# Phychip_board.net
KiCad netlist of a schematic drawn in EAGLE
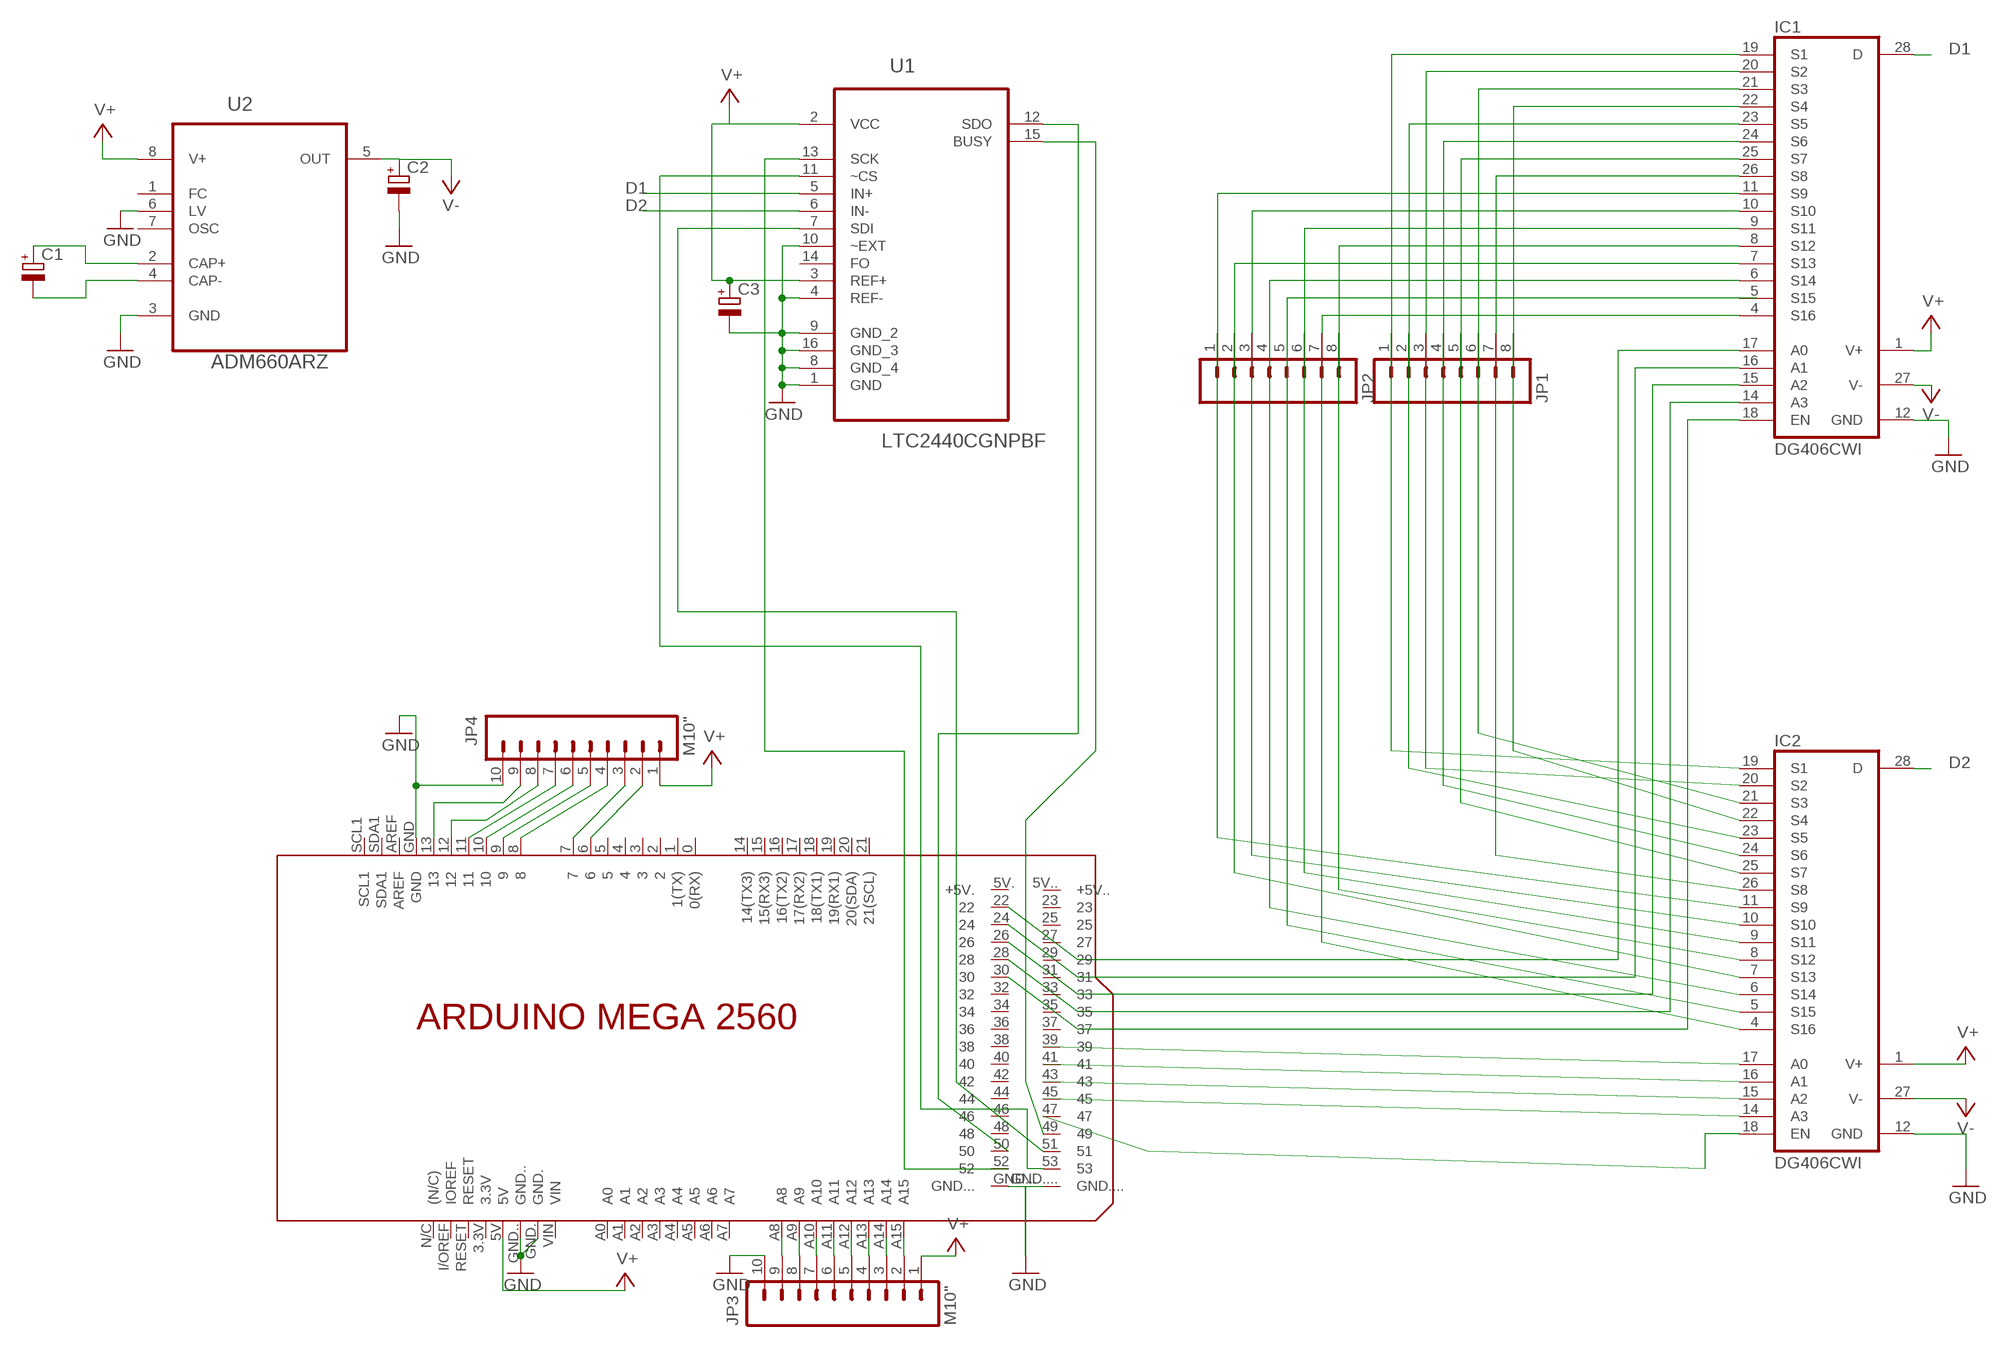
[diagram p0: schematic, sheet 1]

(export (version "E")
  (design (tool "Eeschema 10.0.6"))
  (components
    (comp (ref "C1")
      (value "CPOL-EUE5-6")
      (footprint "eagle-import:E5-6")
      (libsource (lib "eagle-import") (part "CPOL-EUE5-6"))
    )
    (comp (ref "C2")
      (value "CPOL-EUE5-6")
      (footprint "eagle-import:E5-6")
      (libsource (lib "eagle-import") (part "CPOL-EUE5-6"))
    )
    (comp (ref "C3")
      (value "CPOL-EUE5-6")
      (footprint "eagle-import:E5-6")
      (libsource (lib "eagle-import") (part "CPOL-EUE5-6"))
    )
    (comp (ref "IC1")
      (value "DG406CWI")
      (footprint "eagle-import:SO28L")
      (fields (field (name "MF") "MAXIM"))
      (libsource (lib "eagle-import") (part "DG406CWI"))
    )
    (comp (ref "IC2")
      (value "DG406CWI")
      (footprint "eagle-import:SO28L")
      (fields (field (name "MF") "MAXIM"))
      (libsource (lib "eagle-import") (part "DG406CWI"))
    )
    (comp (ref "JP1")
      (value "M08")
      (footprint "eagle-import:1X08")
      (libsource (lib "eagle-import") (part "M08"))
    )
    (comp (ref "JP2")
      (value "M08")
      (footprint "eagle-import:1X08")
      (libsource (lib "eagle-import") (part "M08"))
    )
    (comp (ref "JP3")
      (value "M10\"")
      (footprint "eagle-import:1X10")
      (libsource (lib "eagle-import") (part "M10{dblquote}"))
    )
    (comp (ref "JP4")
      (value "M10\"")
      (footprint "eagle-import:1X10")
      (libsource (lib "eagle-import") (part "M10{dblquote}"))
    )
    (comp (ref "PCB1")
      (value "ARDUINO_MEGA2560")
      (footprint "eagle-import:ARDUINO_MEGA2560")
      (libsource (lib "eagle-import") (part "ARDUINO_MEGA2560"))
    )
    (comp (ref "U1")
      (value "LTC2440CGNPBF")
      (footprint "eagle-import:SOP63P600X175-16N")
      (fields (field (name "MPN") "LTC2440CGN#PBF"))
      (libsource (lib "eagle-import") (part "LTC2440CGNPBF"))
    )
    (comp (ref "U2")
      (value "ADM660ARZ")
      (footprint "eagle-import:SOIC127P600X175-8N")
      (libsource (lib "eagle-import") (part "ADM660ARZ"))
    )
  )
  (nets
    (net (code "1") (name "/D1") (class "Default")
      (node (ref "IC1") (pin "28") (pinfunction "D_28") (pintype "passive"))
      (node (ref "U1") (pin "5") (pinfunction "IN+_5") (pintype "input"))
    )
    (net (code "2") (name "/D2") (class "Default")
      (node (ref "IC2") (pin "28") (pinfunction "D_28") (pintype "passive"))
      (node (ref "U1") (pin "6") (pinfunction "IN-_6") (pintype "input"))
    )
    (net (code "3") (name "GND") (class "Default")
      (node (ref "C2") (pin "-") (pinfunction "-_-") (pintype "passive"))
      (node (ref "C3") (pin "-") (pinfunction "-_-") (pintype "passive"))
      (node (ref "IC1") (pin "12") (pinfunction "GND_12") (pintype "power_in"))
      (node (ref "IC2") (pin "12") (pinfunction "GND_12") (pintype "power_in"))
      (node (ref "JP3") (pin "10") (pinfunction "10_10") (pintype "passive"))
      (node (ref "JP4") (pin "10") (pinfunction "10_10") (pintype "passive"))
      (node (ref "PCB1") (pin "GND") (pinfunction "GND_GND") (pintype "bidirectional"))
      (node (ref "PCB1") (pin "GND.") (pinfunction "GND._GND.") (pintype "bidirectional"))
      (node (ref "PCB1") (pin "GND..") (pinfunction "GND.._GND..") (pintype "bidirectional"))
      (node (ref "PCB1") (pin "GND...") (pinfunction "GND..._GND...") (pintype "bidirectional"))
      (node (ref "PCB1") (pin "GND....") (pinfunction "GND...._GND....") (pintype "bidirectional"))
      (node (ref "U1") (pin "1") (pinfunction "GND_1") (pintype "passive"))
      (node (ref "U1") (pin "10") (pinfunction "~{EXT}_10") (pintype "input"))
      (node (ref "U1") (pin "16") (pinfunction "GND_3_16") (pintype "passive"))
      (node (ref "U1") (pin "4") (pinfunction "REF-_4") (pintype "input"))
      (node (ref "U1") (pin "8") (pinfunction "GND_4_8") (pintype "passive"))
      (node (ref "U1") (pin "9") (pinfunction "GND_2_9") (pintype "passive"))
      (node (ref "U2") (pin "3") (pinfunction "GND_3") (pintype "passive"))
      (node (ref "U2") (pin "6") (pinfunction "LV_6") (pintype "input"))
    )
    (net (code "4") (name "Net-(IC1-A0)") (class "Default")
      (node (ref "IC1") (pin "17") (pinfunction "A0_17") (pintype "input"))
      (node (ref "PCB1") (pin "22") (pinfunction "22_22") (pintype "bidirectional"))
    )
    (net (code "5") (name "Net-(IC1-A1)") (class "Default")
      (node (ref "IC1") (pin "16") (pinfunction "A1_16") (pintype "input"))
      (node (ref "PCB1") (pin "24") (pinfunction "24_24") (pintype "bidirectional"))
    )
    (net (code "6") (name "Net-(IC1-A2)") (class "Default")
      (node (ref "IC1") (pin "15") (pinfunction "A2_15") (pintype "input"))
      (node (ref "PCB1") (pin "26") (pinfunction "26_26") (pintype "bidirectional"))
    )
    (net (code "7") (name "Net-(IC1-A3)") (class "Default")
      (node (ref "IC1") (pin "14") (pinfunction "A3_14") (pintype "input"))
      (node (ref "PCB1") (pin "28") (pinfunction "28_28") (pintype "bidirectional"))
    )
    (net (code "8") (name "Net-(IC1-EN)") (class "Default")
      (node (ref "IC1") (pin "18") (pinfunction "EN_18") (pintype "input"))
      (node (ref "PCB1") (pin "30") (pinfunction "30_30") (pintype "bidirectional"))
    )
    (net (code "9") (name "Net-(IC1-S1)") (class "Default")
      (node (ref "IC1") (pin "19") (pinfunction "S1_19") (pintype "passive"))
      (node (ref "IC2") (pin "19") (pinfunction "S1_19") (pintype "passive"))
      (node (ref "JP1") (pin "1") (pinfunction "1_1") (pintype "passive"))
    )
    (net (code "10") (name "Net-(IC1-S2)") (class "Default")
      (node (ref "IC1") (pin "20") (pinfunction "S2_20") (pintype "passive"))
      (node (ref "IC2") (pin "20") (pinfunction "S2_20") (pintype "passive"))
      (node (ref "JP1") (pin "3") (pinfunction "3_3") (pintype "passive"))
    )
    (net (code "11") (name "Net-(IC1-S3)") (class "Default")
      (node (ref "IC1") (pin "21") (pinfunction "S3_21") (pintype "passive"))
      (node (ref "IC2") (pin "21") (pinfunction "S3_21") (pintype "passive"))
      (node (ref "JP1") (pin "6") (pinfunction "6_6") (pintype "passive"))
    )
    (net (code "12") (name "Net-(IC1-S4)") (class "Default")
      (node (ref "IC1") (pin "22") (pinfunction "S4_22") (pintype "passive"))
      (node (ref "IC2") (pin "22") (pinfunction "S4_22") (pintype "passive"))
      (node (ref "JP1") (pin "8") (pinfunction "8_8") (pintype "passive"))
    )
    (net (code "13") (name "Net-(IC1-S5)") (class "Default")
      (node (ref "IC1") (pin "23") (pinfunction "S5_23") (pintype "passive"))
      (node (ref "IC2") (pin "23") (pinfunction "S5_23") (pintype "passive"))
      (node (ref "JP1") (pin "2") (pinfunction "2_2") (pintype "passive"))
    )
    (net (code "14") (name "Net-(IC1-S6)") (class "Default")
      (node (ref "IC1") (pin "24") (pinfunction "S6_24") (pintype "passive"))
      (node (ref "IC2") (pin "24") (pinfunction "S6_24") (pintype "passive"))
      (node (ref "JP1") (pin "4") (pinfunction "4_4") (pintype "passive"))
    )
    (net (code "15") (name "Net-(IC1-S7)") (class "Default")
      (node (ref "IC1") (pin "25") (pinfunction "S7_25") (pintype "passive"))
      (node (ref "IC2") (pin "25") (pinfunction "S7_25") (pintype "passive"))
      (node (ref "JP1") (pin "5") (pinfunction "5_5") (pintype "passive"))
    )
    (net (code "16") (name "Net-(IC1-S8)") (class "Default")
      (node (ref "IC1") (pin "26") (pinfunction "S8_26") (pintype "passive"))
      (node (ref "IC2") (pin "26") (pinfunction "S8_26") (pintype "passive"))
      (node (ref "JP1") (pin "7") (pinfunction "7_7") (pintype "passive"))
    )
    (net (code "17") (name "Net-(IC1-S9)") (class "Default")
      (node (ref "IC1") (pin "11") (pinfunction "S9_11") (pintype "passive"))
      (node (ref "IC2") (pin "11") (pinfunction "S9_11") (pintype "passive"))
      (node (ref "JP2") (pin "1") (pinfunction "1_1") (pintype "passive"))
    )
    (net (code "18") (name "Net-(IC1-S10)") (class "Default")
      (node (ref "IC1") (pin "10") (pinfunction "S10_10") (pintype "passive"))
      (node (ref "IC2") (pin "10") (pinfunction "S10_10") (pintype "passive"))
      (node (ref "JP2") (pin "3") (pinfunction "3_3") (pintype "passive"))
    )
    (net (code "19") (name "Net-(IC1-S11)") (class "Default")
      (node (ref "IC1") (pin "9") (pinfunction "S11_9") (pintype "passive"))
      (node (ref "IC2") (pin "9") (pinfunction "S11_9") (pintype "passive"))
      (node (ref "JP2") (pin "6") (pinfunction "6_6") (pintype "passive"))
    )
    (net (code "20") (name "Net-(IC1-S12)") (class "Default")
      (node (ref "IC1") (pin "8") (pinfunction "S12_8") (pintype "passive"))
      (node (ref "IC2") (pin "8") (pinfunction "S12_8") (pintype "passive"))
      (node (ref "JP2") (pin "8") (pinfunction "8_8") (pintype "passive"))
    )
    (net (code "21") (name "Net-(IC1-S13)") (class "Default")
      (node (ref "IC1") (pin "7") (pinfunction "S13_7") (pintype "passive"))
      (node (ref "IC2") (pin "7") (pinfunction "S13_7") (pintype "passive"))
      (node (ref "JP2") (pin "2") (pinfunction "2_2") (pintype "passive"))
    )
    (net (code "22") (name "Net-(IC1-S14)") (class "Default")
      (node (ref "IC1") (pin "6") (pinfunction "S14_6") (pintype "passive"))
      (node (ref "IC2") (pin "6") (pinfunction "S14_6") (pintype "passive"))
      (node (ref "JP2") (pin "4") (pinfunction "4_4") (pintype "passive"))
    )
    (net (code "23") (name "Net-(IC1-S16)") (class "Default")
      (node (ref "IC1") (pin "4") (pinfunction "S16_4") (pintype "passive"))
      (node (ref "IC2") (pin "4") (pinfunction "S16_4") (pintype "passive"))
      (node (ref "JP2") (pin "7") (pinfunction "7_7") (pintype "passive"))
    )
    (net (code "24") (name "Net-(IC2-A0)") (class "Default")
      (node (ref "IC2") (pin "17") (pinfunction "A0_17") (pintype "input"))
      (node (ref "PCB1") (pin "39") (pinfunction "39_39") (pintype "bidirectional"))
    )
    (net (code "25") (name "Net-(IC2-A1)") (class "Default")
      (node (ref "IC2") (pin "16") (pinfunction "A1_16") (pintype "input"))
      (node (ref "PCB1") (pin "41") (pinfunction "41_41") (pintype "bidirectional"))
    )
    (net (code "26") (name "Net-(IC2-A2)") (class "Default")
      (node (ref "IC2") (pin "15") (pinfunction "A2_15") (pintype "input"))
      (node (ref "PCB1") (pin "43") (pinfunction "43_43") (pintype "bidirectional"))
    )
    (net (code "27") (name "Net-(IC2-A3)") (class "Default")
      (node (ref "IC2") (pin "14") (pinfunction "A3_14") (pintype "input"))
      (node (ref "PCB1") (pin "45") (pinfunction "45_45") (pintype "bidirectional"))
    )
    (net (code "28") (name "Net-(IC2-EN)") (class "Default")
      (node (ref "IC2") (pin "18") (pinfunction "EN_18") (pintype "input"))
      (node (ref "PCB1") (pin "47") (pinfunction "47_47") (pintype "bidirectional"))
    )
    (net (code "29") (name "Net-(IC2-S15)") (class "Default")
      (node (ref "IC2") (pin "5") (pinfunction "S15_5") (pintype "passive"))
      (node (ref "JP2") (pin "5") (pinfunction "5_5") (pintype "passive"))
    )
    (net (code "30") (name "Net-(JP3-Pad2)") (class "Default")
      (node (ref "JP3") (pin "2") (pinfunction "2_2") (pintype "passive"))
      (node (ref "PCB1") (pin "A15") (pinfunction "A15_A15") (pintype "bidirectional"))
    )
    (net (code "31") (name "Net-(JP3-Pad3)") (class "Default")
      (node (ref "JP3") (pin "3") (pinfunction "3_3") (pintype "passive"))
      (node (ref "PCB1") (pin "A14") (pinfunction "A14_A14") (pintype "bidirectional"))
    )
    (net (code "32") (name "Net-(JP3-Pad4)") (class "Default")
      (node (ref "JP3") (pin "4") (pinfunction "4_4") (pintype "passive"))
      (node (ref "PCB1") (pin "A13") (pinfunction "A13_A13") (pintype "bidirectional"))
    )
    (net (code "33") (name "Net-(JP3-Pad5)") (class "Default")
      (node (ref "JP3") (pin "5") (pinfunction "5_5") (pintype "passive"))
      (node (ref "PCB1") (pin "A12") (pinfunction "A12_A12") (pintype "bidirectional"))
    )
    (net (code "34") (name "Net-(JP3-Pad6)") (class "Default")
      (node (ref "JP3") (pin "6") (pinfunction "6_6") (pintype "passive"))
      (node (ref "PCB1") (pin "A11") (pinfunction "A11_A11") (pintype "bidirectional"))
    )
    (net (code "35") (name "Net-(JP3-Pad7)") (class "Default")
      (node (ref "JP3") (pin "7") (pinfunction "7_7") (pintype "passive"))
      (node (ref "PCB1") (pin "A10") (pinfunction "A10_A10") (pintype "bidirectional"))
    )
    (net (code "36") (name "Net-(JP3-Pad8)") (class "Default")
      (node (ref "JP3") (pin "8") (pinfunction "8_8") (pintype "passive"))
      (node (ref "PCB1") (pin "A9") (pinfunction "A9_A9") (pintype "bidirectional"))
    )
    (net (code "37") (name "Net-(JP3-Pad9)") (class "Default")
      (node (ref "JP3") (pin "9") (pinfunction "9_9") (pintype "passive"))
      (node (ref "PCB1") (pin "A8") (pinfunction "A8_A8") (pintype "bidirectional"))
    )
    (net (code "38") (name "Net-(JP4-Pad2)") (class "Default")
      (node (ref "JP4") (pin "2") (pinfunction "2_2") (pintype "passive"))
      (node (ref "PCB1") (pin "6") (pinfunction "6_6") (pintype "bidirectional"))
    )
    (net (code "39") (name "Net-(JP4-Pad3)") (class "Default")
      (node (ref "JP4") (pin "3") (pinfunction "3_3") (pintype "passive"))
      (node (ref "PCB1") (pin "7") (pinfunction "7_7") (pintype "bidirectional"))
    )
    (net (code "40") (name "Net-(JP4-Pad4)") (class "Default")
      (node (ref "JP4") (pin "4") (pinfunction "4_4") (pintype "passive"))
      (node (ref "PCB1") (pin "8") (pinfunction "8_8") (pintype "bidirectional"))
    )
    (net (code "41") (name "Net-(JP4-Pad5)") (class "Default")
      (node (ref "JP4") (pin "5") (pinfunction "5_5") (pintype "passive"))
      (node (ref "PCB1") (pin "9") (pinfunction "9_9") (pintype "bidirectional"))
    )
    (net (code "42") (name "Net-(JP4-Pad6)") (class "Default")
      (node (ref "JP4") (pin "6") (pinfunction "6_6") (pintype "passive"))
      (node (ref "PCB1") (pin "10") (pinfunction "10_10") (pintype "bidirectional"))
    )
    (net (code "43") (name "Net-(JP4-Pad7)") (class "Default")
      (node (ref "JP4") (pin "7") (pinfunction "7_7") (pintype "passive"))
      (node (ref "PCB1") (pin "11") (pinfunction "11_11") (pintype "bidirectional"))
    )
    (net (code "44") (name "Net-(JP4-Pad8)") (class "Default")
      (node (ref "JP4") (pin "8") (pinfunction "8_8") (pintype "passive"))
      (node (ref "PCB1") (pin "12") (pinfunction "12_12") (pintype "bidirectional"))
    )
    (net (code "45") (name "Net-(JP4-Pad9)") (class "Default")
      (node (ref "JP4") (pin "9") (pinfunction "9_9") (pintype "passive"))
      (node (ref "PCB1") (pin "13") (pinfunction "13_13") (pintype "bidirectional"))
    )
    (net (code "46") (name "Net-(U1-BUSY)") (class "Default")
      (node (ref "PCB1") (pin "49") (pinfunction "49_49") (pintype "bidirectional"))
      (node (ref "U1") (pin "15") (pinfunction "BUSY_15") (pintype "output"))
    )
    (net (code "47") (name "Net-(U1-SCK)") (class "Default")
      (node (ref "PCB1") (pin "52") (pinfunction "52_52") (pintype "bidirectional"))
      (node (ref "U1") (pin "13") (pinfunction "SCK_13") (pintype "input"))
    )
    (net (code "48") (name "Net-(U1-SDI)") (class "Default")
      (node (ref "PCB1") (pin "51") (pinfunction "51_51") (pintype "bidirectional"))
      (node (ref "U1") (pin "7") (pinfunction "SDI_7") (pintype "input"))
    )
    (net (code "49") (name "Net-(U1-SDO)") (class "Default")
      (node (ref "PCB1") (pin "50") (pinfunction "50_50") (pintype "bidirectional"))
      (node (ref "U1") (pin "12") (pinfunction "SDO_12") (pintype "output"))
    )
    (net (code "50") (name "Net-(U1-~{CS})") (class "Default")
      (node (ref "PCB1") (pin "53") (pinfunction "53_53") (pintype "bidirectional"))
      (node (ref "U1") (pin "11") (pinfunction "~{CS}_11") (pintype "input"))
    )
    (net (code "51") (name "Net-(U2-CAP+)") (class "Default")
      (node (ref "C1") (pin "+") (pinfunction "+_+") (pintype "passive"))
      (node (ref "U2") (pin "2") (pinfunction "CAP+_2") (pintype "input"))
    )
    (net (code "52") (name "Net-(U2-CAP-)") (class "Default")
      (node (ref "C1") (pin "-") (pinfunction "-_-") (pintype "passive"))
      (node (ref "U2") (pin "4") (pinfunction "CAP-_4") (pintype "input"))
    )
    (net (code "53") (name "V+") (class "Default")
      (node (ref "C3") (pin "+") (pinfunction "+_+") (pintype "passive"))
      (node (ref "IC1") (pin "1") (pinfunction "V+_1") (pintype "power_in"))
      (node (ref "IC2") (pin "1") (pinfunction "V+_1") (pintype "power_in"))
      (node (ref "JP3") (pin "1") (pinfunction "1_1") (pintype "passive"))
      (node (ref "JP4") (pin "1") (pinfunction "1_1") (pintype "passive"))
      (node (ref "PCB1") (pin "5V") (pinfunction "5V_5V") (pintype "bidirectional"))
      (node (ref "U1") (pin "2") (pinfunction "VCC_2") (pintype "power_in"))
      (node (ref "U1") (pin "3") (pinfunction "REF+_3") (pintype "input"))
      (node (ref "U2") (pin "8") (pinfunction "V+_8") (pintype "power_in"))
    )
    (net (code "54") (name "V-") (class "Default")
      (node (ref "C2") (pin "+") (pinfunction "+_+") (pintype "passive"))
      (node (ref "IC1") (pin "27") (pinfunction "V-_27") (pintype "power_in"))
      (node (ref "IC2") (pin "27") (pinfunction "V-_27") (pintype "power_in"))
      (node (ref "U2") (pin "5") (pinfunction "OUT_5") (pintype "output"))
    )
    (net (code "55") (name "unconnected-(IC1-S15-Pad5)") (class "Default")
      (node (ref "IC1") (pin "5") (pinfunction "S15_5") (pintype "passive"))
    )
    (net (code "56") (name "unconnected-(PCB1-(N{slash}C)-PadN{slash}C)") (class "Default")
      (node (ref "PCB1") (pin "N/C") (pinfunction "(N/C)_N/C") (pintype "bidirectional"))
    )
    (net (code "57") (name "unconnected-(PCB1-+5V.-Pad5V.)") (class "Default")
      (node (ref "PCB1") (pin "5V.") (pinfunction "+5V._5V.") (pintype "bidirectional"))
    )
    (net (code "58") (name "unconnected-(PCB1-+5V..-Pad5V..)") (class "Default")
      (node (ref "PCB1") (pin "5V..") (pinfunction "+5V.._5V..") (pintype "bidirectional"))
    )
    (net (code "59") (name "unconnected-(PCB1-0(RX)-Pad0)") (class "Default")
      (node (ref "PCB1") (pin "0") (pinfunction "0(RX)_0") (pintype "bidirectional"))
    )
    (net (code "60") (name "unconnected-(PCB1-1(TX)-Pad1)") (class "Default")
      (node (ref "PCB1") (pin "1") (pinfunction "1(TX)_1") (pintype "bidirectional"))
    )
    (net (code "61") (name "unconnected-(PCB1-14(TX3)-Pad14)") (class "Default")
      (node (ref "PCB1") (pin "14") (pinfunction "14(TX3)_14") (pintype "bidirectional"))
    )
    (net (code "62") (name "unconnected-(PCB1-15(RX3)-Pad15)") (class "Default")
      (node (ref "PCB1") (pin "15") (pinfunction "15(RX3)_15") (pintype "bidirectional"))
    )
    (net (code "63") (name "unconnected-(PCB1-16(TX2)-Pad16)") (class "Default")
      (node (ref "PCB1") (pin "16") (pinfunction "16(TX2)_16") (pintype "bidirectional"))
    )
    (net (code "64") (name "unconnected-(PCB1-17(RX2)-Pad17)") (class "Default")
      (node (ref "PCB1") (pin "17") (pinfunction "17(RX2)_17") (pintype "bidirectional"))
    )
    (net (code "65") (name "unconnected-(PCB1-18(TX1)-Pad18)") (class "Default")
      (node (ref "PCB1") (pin "18") (pinfunction "18(TX1)_18") (pintype "bidirectional"))
    )
    (net (code "66") (name "unconnected-(PCB1-19(RX1)-Pad19)") (class "Default")
      (node (ref "PCB1") (pin "19") (pinfunction "19(RX1)_19") (pintype "bidirectional"))
    )
    (net (code "67") (name "unconnected-(PCB1-20(SDA)-Pad20)") (class "Default")
      (node (ref "PCB1") (pin "20") (pinfunction "20(SDA)_20") (pintype "bidirectional"))
    )
    (net (code "68") (name "unconnected-(PCB1-21(SCL)-Pad21)") (class "Default")
      (node (ref "PCB1") (pin "21") (pinfunction "21(SCL)_21") (pintype "bidirectional"))
    )
    (net (code "69") (name "unconnected-(PCB1-IOREF-PadI{slash}OREF)") (class "Default")
      (node (ref "PCB1") (pin "I/OREF") (pinfunction "IOREF_I/OREF") (pintype "bidirectional"))
    )
    (net (code "70") (name "unconnected-(PCB1-Pad2)") (class "Default")
      (node (ref "PCB1") (pin "2") (pinfunction "2_2") (pintype "bidirectional"))
    )
    (net (code "71") (name "unconnected-(PCB1-Pad3)") (class "Default")
      (node (ref "PCB1") (pin "3") (pinfunction "3_3") (pintype "bidirectional"))
    )
    (net (code "72") (name "unconnected-(PCB1-Pad3.3V)") (class "Default")
      (node (ref "PCB1") (pin "3.3V") (pinfunction "3.3V_3.3V") (pintype "bidirectional"))
    )
    (net (code "73") (name "unconnected-(PCB1-Pad4)") (class "Default")
      (node (ref "PCB1") (pin "4") (pinfunction "4_4") (pintype "bidirectional"))
    )
    (net (code "74") (name "unconnected-(PCB1-Pad5)") (class "Default")
      (node (ref "PCB1") (pin "5") (pinfunction "5_5") (pintype "bidirectional"))
    )
    (net (code "75") (name "unconnected-(PCB1-Pad23)") (class "Default")
      (node (ref "PCB1") (pin "23") (pinfunction "23_23") (pintype "bidirectional"))
    )
    (net (code "76") (name "unconnected-(PCB1-Pad25)") (class "Default")
      (node (ref "PCB1") (pin "25") (pinfunction "25_25") (pintype "bidirectional"))
    )
    (net (code "77") (name "unconnected-(PCB1-Pad27)") (class "Default")
      (node (ref "PCB1") (pin "27") (pinfunction "27_27") (pintype "bidirectional"))
    )
    (net (code "78") (name "unconnected-(PCB1-Pad29)") (class "Default")
      (node (ref "PCB1") (pin "29") (pinfunction "29_29") (pintype "bidirectional"))
    )
    (net (code "79") (name "unconnected-(PCB1-Pad31)") (class "Default")
      (node (ref "PCB1") (pin "31") (pinfunction "31_31") (pintype "bidirectional"))
    )
    (net (code "80") (name "unconnected-(PCB1-Pad32)") (class "Default")
      (node (ref "PCB1") (pin "32") (pinfunction "32_32") (pintype "bidirectional"))
    )
    (net (code "81") (name "unconnected-(PCB1-Pad33)") (class "Default")
      (node (ref "PCB1") (pin "33") (pinfunction "33_33") (pintype "bidirectional"))
    )
    (net (code "82") (name "unconnected-(PCB1-Pad34)") (class "Default")
      (node (ref "PCB1") (pin "34") (pinfunction "34_34") (pintype "bidirectional"))
    )
    (net (code "83") (name "unconnected-(PCB1-Pad35)") (class "Default")
      (node (ref "PCB1") (pin "35") (pinfunction "35_35") (pintype "bidirectional"))
    )
    (net (code "84") (name "unconnected-(PCB1-Pad36)") (class "Default")
      (node (ref "PCB1") (pin "36") (pinfunction "36_36") (pintype "bidirectional"))
    )
    (net (code "85") (name "unconnected-(PCB1-Pad37)") (class "Default")
      (node (ref "PCB1") (pin "37") (pinfunction "37_37") (pintype "bidirectional"))
    )
    (net (code "86") (name "unconnected-(PCB1-Pad38)") (class "Default")
      (node (ref "PCB1") (pin "38") (pinfunction "38_38") (pintype "bidirectional"))
    )
    (net (code "87") (name "unconnected-(PCB1-Pad40)") (class "Default")
      (node (ref "PCB1") (pin "40") (pinfunction "40_40") (pintype "bidirectional"))
    )
    (net (code "88") (name "unconnected-(PCB1-Pad42)") (class "Default")
      (node (ref "PCB1") (pin "42") (pinfunction "42_42") (pintype "bidirectional"))
    )
    (net (code "89") (name "unconnected-(PCB1-Pad44)") (class "Default")
      (node (ref "PCB1") (pin "44") (pinfunction "44_44") (pintype "bidirectional"))
    )
    (net (code "90") (name "unconnected-(PCB1-Pad46)") (class "Default")
      (node (ref "PCB1") (pin "46") (pinfunction "46_46") (pintype "bidirectional"))
    )
    (net (code "91") (name "unconnected-(PCB1-Pad48)") (class "Default")
      (node (ref "PCB1") (pin "48") (pinfunction "48_48") (pintype "bidirectional"))
    )
    (net (code "92") (name "unconnected-(PCB1-PadA0)") (class "Default")
      (node (ref "PCB1") (pin "A0") (pinfunction "A0_A0") (pintype "bidirectional"))
    )
    (net (code "93") (name "unconnected-(PCB1-PadA1)") (class "Default")
      (node (ref "PCB1") (pin "A1") (pinfunction "A1_A1") (pintype "bidirectional"))
    )
    (net (code "94") (name "unconnected-(PCB1-PadA2)") (class "Default")
      (node (ref "PCB1") (pin "A2") (pinfunction "A2_A2") (pintype "bidirectional"))
    )
    (net (code "95") (name "unconnected-(PCB1-PadA3)") (class "Default")
      (node (ref "PCB1") (pin "A3") (pinfunction "A3_A3") (pintype "bidirectional"))
    )
    (net (code "96") (name "unconnected-(PCB1-PadA4)") (class "Default")
      (node (ref "PCB1") (pin "A4") (pinfunction "A4_A4") (pintype "bidirectional"))
    )
    (net (code "97") (name "unconnected-(PCB1-PadA5)") (class "Default")
      (node (ref "PCB1") (pin "A5") (pinfunction "A5_A5") (pintype "bidirectional"))
    )
    (net (code "98") (name "unconnected-(PCB1-PadA6)") (class "Default")
      (node (ref "PCB1") (pin "A6") (pinfunction "A6_A6") (pintype "bidirectional"))
    )
    (net (code "99") (name "unconnected-(PCB1-PadA7)") (class "Default")
      (node (ref "PCB1") (pin "A7") (pinfunction "A7_A7") (pintype "bidirectional"))
    )
    (net (code "100") (name "unconnected-(PCB1-PadAREF)") (class "Default")
      (node (ref "PCB1") (pin "AREF") (pinfunction "AREF_AREF") (pintype "bidirectional"))
    )
    (net (code "101") (name "unconnected-(PCB1-PadRESET)") (class "Default")
      (node (ref "PCB1") (pin "RESET") (pinfunction "RESET_RESET") (pintype "bidirectional"))
    )
    (net (code "102") (name "unconnected-(PCB1-PadSCL1)") (class "Default")
      (node (ref "PCB1") (pin "SCL1") (pinfunction "SCL1_SCL1") (pintype "bidirectional"))
    )
    (net (code "103") (name "unconnected-(PCB1-PadSDA1)") (class "Default")
      (node (ref "PCB1") (pin "SDA1") (pinfunction "SDA1_SDA1") (pintype "bidirectional"))
    )
    (net (code "104") (name "unconnected-(PCB1-PadVIN)") (class "Default")
      (node (ref "PCB1") (pin "VIN") (pinfunction "VIN_VIN") (pintype "bidirectional"))
    )
    (net (code "105") (name "unconnected-(U1-FO-Pad14)") (class "Default")
      (node (ref "U1") (pin "14") (pinfunction "FO_14") (pintype "input"))
    )
    (net (code "106") (name "unconnected-(U2-FC-Pad1)") (class "Default")
      (node (ref "U2") (pin "1") (pinfunction "FC_1") (pintype "input"))
    )
    (net (code "107") (name "unconnected-(U2-OSC-Pad7)") (class "Default")
      (node (ref "U2") (pin "7") (pinfunction "OSC_7") (pintype "input"))
    )
  )
)
